# schemat1.net
KiCad netlist of a schematic drawn in EAGLE
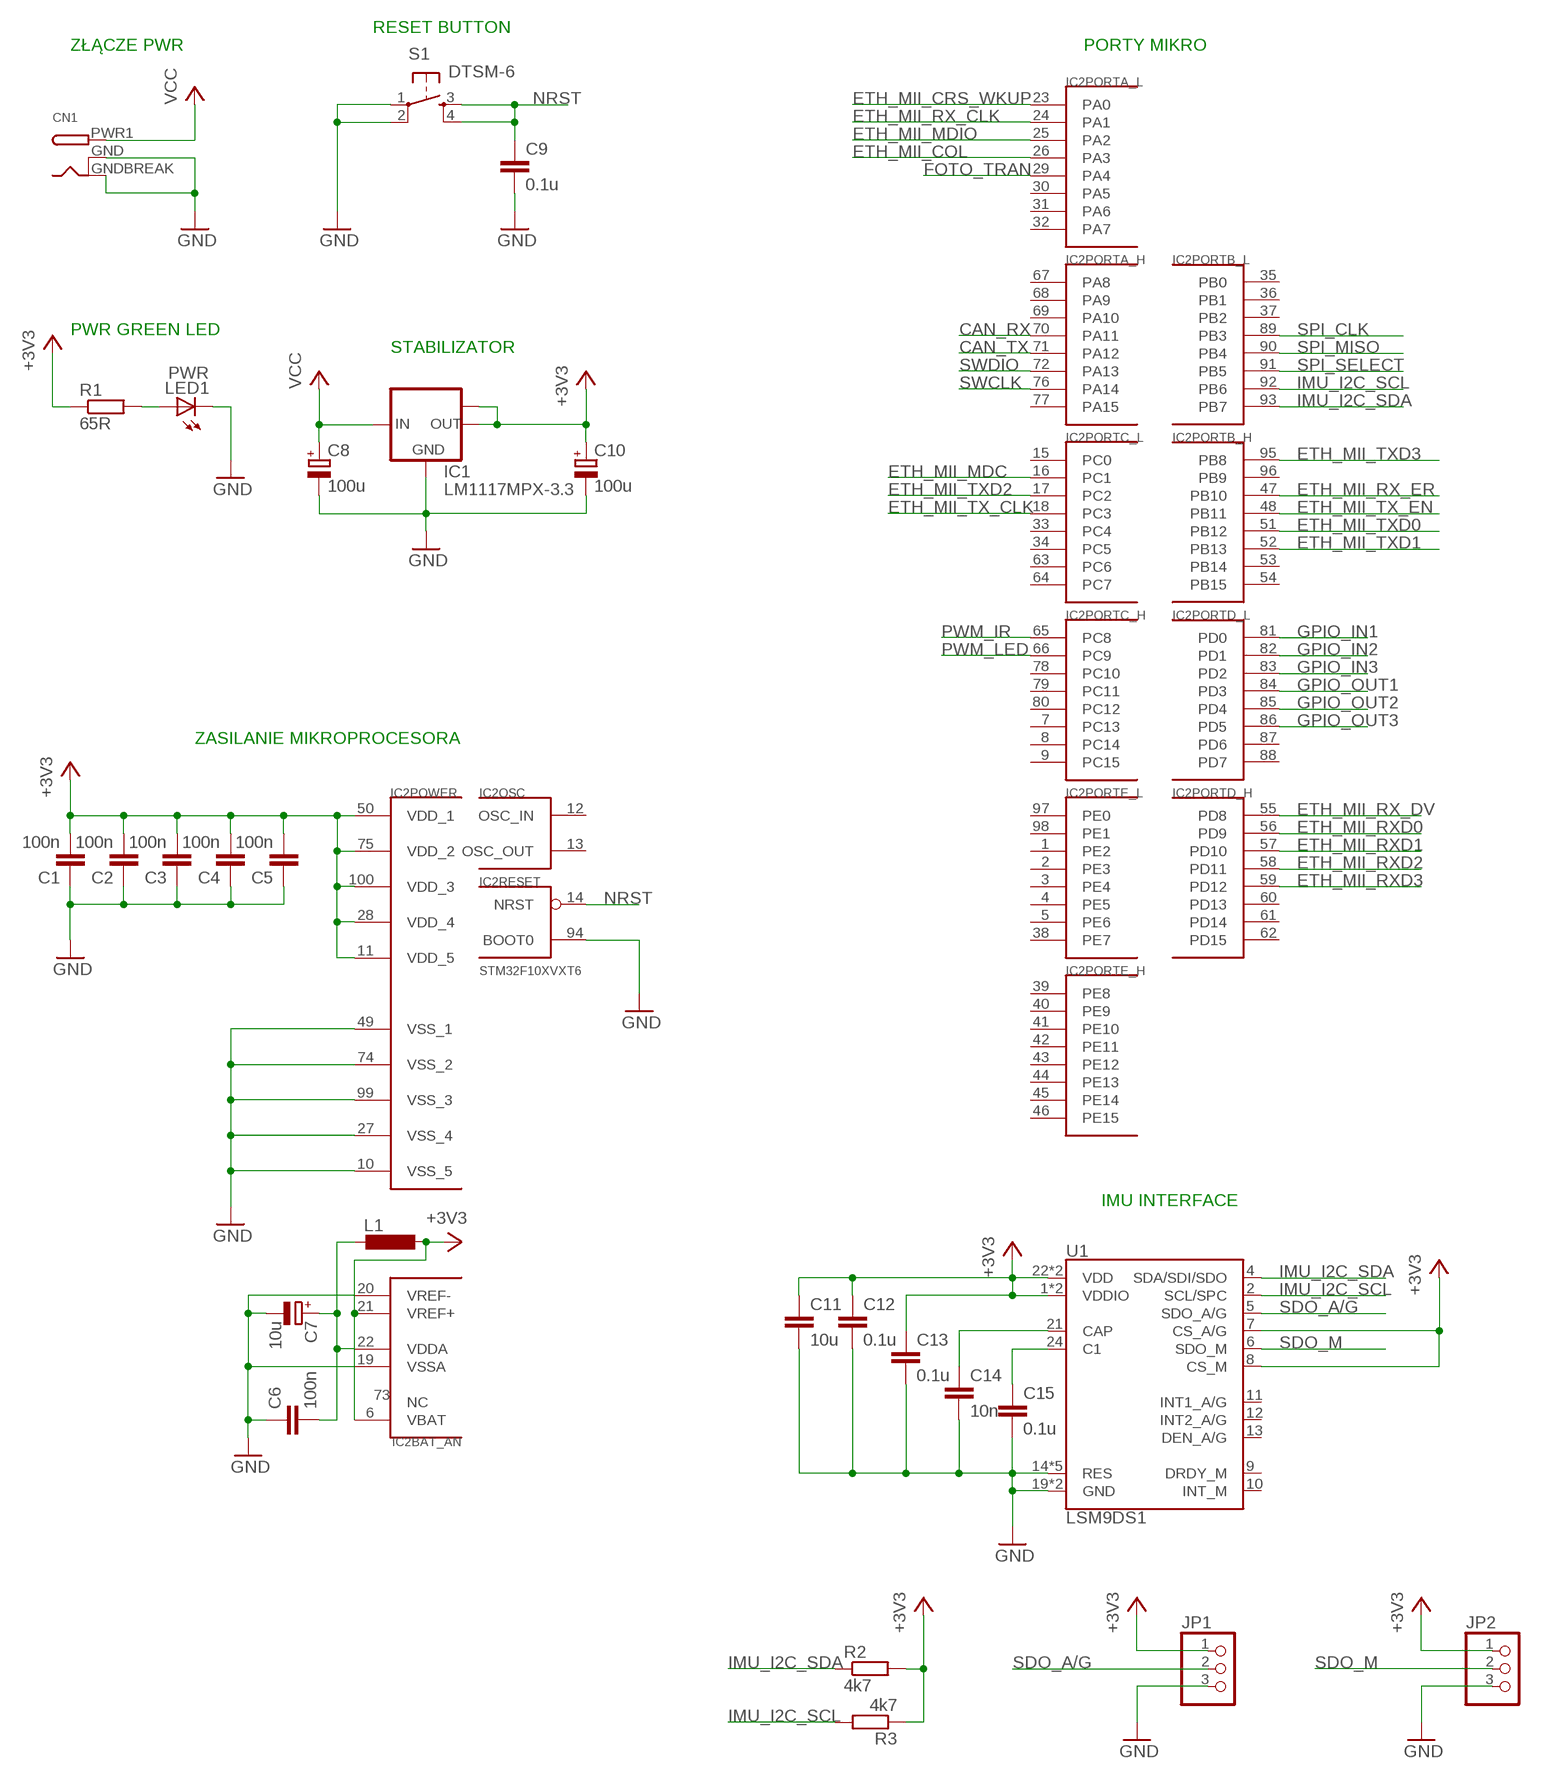
[diagram p0: schematic, sheet 1, part 1 of 2]
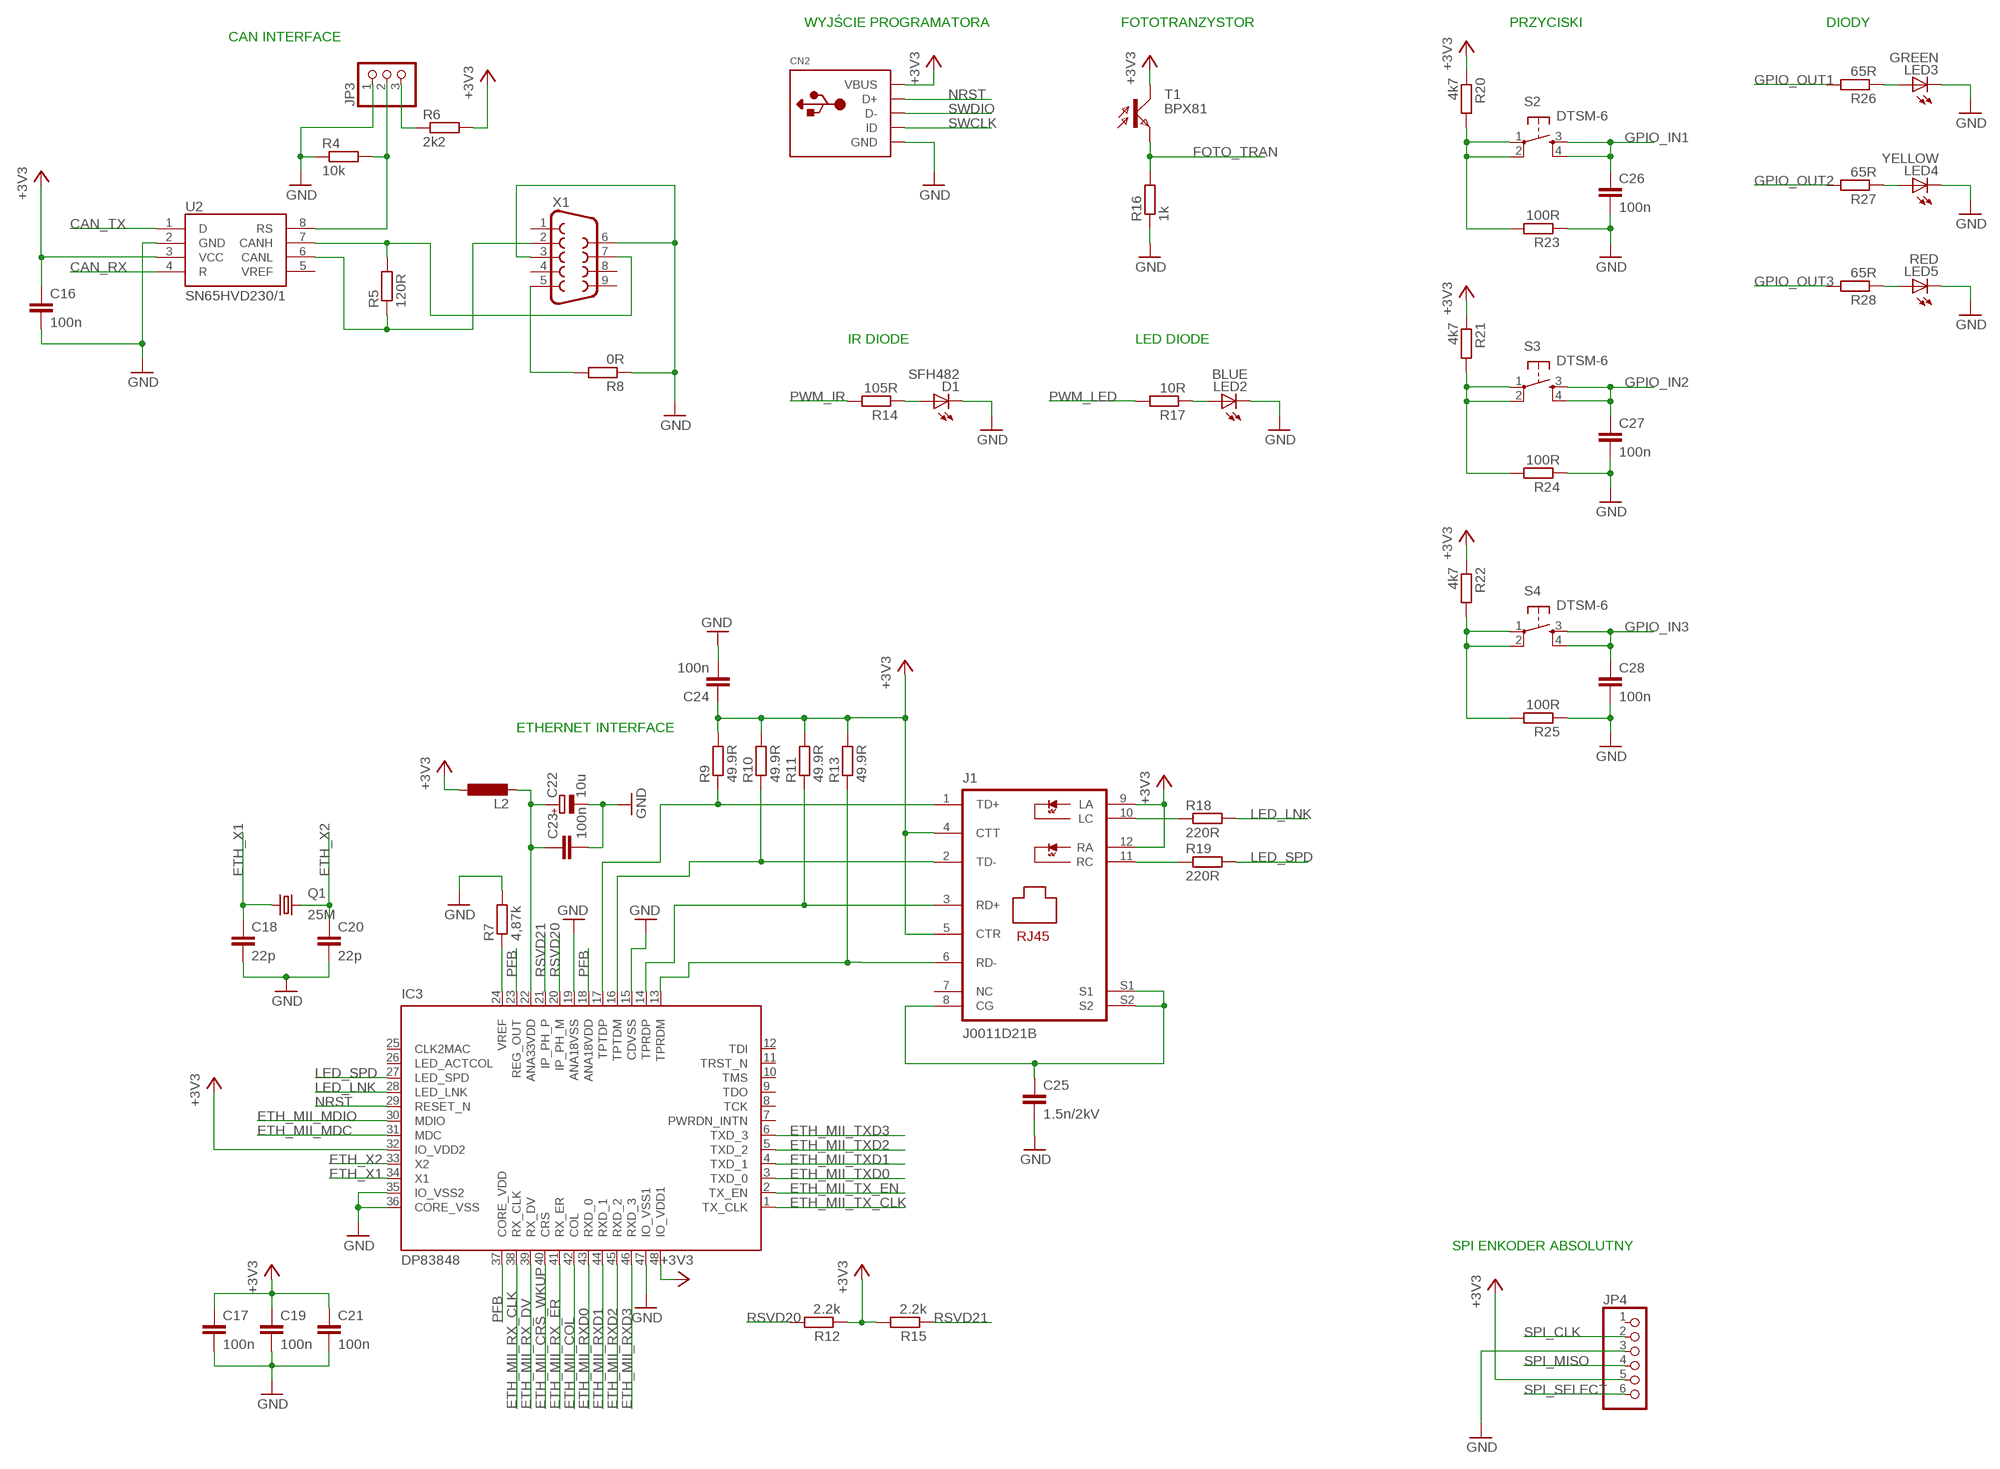
[diagram p1: schematic, sheet 1, part 2 of 2]

(export (version "E")
  (design (tool "Eeschema 10.0.6"))
  (components
    (comp (ref "C1")
      (value "100n")
      (footprint "eagle-import:C0805")
      (libsource (lib "eagle-import") (part "C-EUC0805"))
    )
    (comp (ref "C2")
      (value "100n")
      (footprint "eagle-import:C0805")
      (libsource (lib "eagle-import") (part "C-EUC0805"))
    )
    (comp (ref "C3")
      (value "100n")
      (footprint "eagle-import:C0805")
      (libsource (lib "eagle-import") (part "C-EUC0805"))
    )
    (comp (ref "C4")
      (value "100n")
      (footprint "eagle-import:C0805")
      (libsource (lib "eagle-import") (part "C-EUC0805"))
    )
    (comp (ref "C5")
      (value "100n")
      (footprint "eagle-import:C0805")
      (libsource (lib "eagle-import") (part "C-EUC0805"))
    )
    (comp (ref "C6")
      (value "100n")
      (footprint "eagle-import:C0805")
      (libsource (lib "eagle-import") (part "C-EUC0805"))
    )
    (comp (ref "C7")
      (value "10u")
      (footprint "eagle-import:PANASONIC_C")
      (libsource (lib "eagle-import") (part "CPOL-EUC"))
    )
    (comp (ref "C8")
      (value "100u")
      (footprint "eagle-import:PANASONIC_C")
      (libsource (lib "eagle-import") (part "CPOL-EUC"))
    )
    (comp (ref "C9")
      (value "0.1u")
      (footprint "eagle-import:C0805")
      (libsource (lib "eagle-import") (part "C-EUC0805"))
    )
    (comp (ref "C10")
      (value "100u")
      (footprint "eagle-import:PANASONIC_C")
      (libsource (lib "eagle-import") (part "CPOL-EUC"))
    )
    (comp (ref "C11")
      (value "10u")
      (footprint "eagle-import:C0805")
      (libsource (lib "eagle-import") (part "C-EUC0805"))
    )
    (comp (ref "C12")
      (value "0.1u")
      (footprint "eagle-import:C0805")
      (libsource (lib "eagle-import") (part "C-EUC0805"))
    )
    (comp (ref "C13")
      (value "0.1u")
      (footprint "eagle-import:C0805")
      (libsource (lib "eagle-import") (part "C-EUC0805"))
    )
    (comp (ref "C14")
      (value "10n")
      (footprint "eagle-import:C0805")
      (libsource (lib "eagle-import") (part "C-EUC0805"))
    )
    (comp (ref "C15")
      (value "0.1u")
      (footprint "eagle-import:C0805")
      (libsource (lib "eagle-import") (part "C-EUC0805"))
    )
    (comp (ref "C16")
      (value "100n")
      (footprint "eagle-import:C0805")
      (libsource (lib "eagle-import") (part "C-EUC0805"))
    )
    (comp (ref "C17")
      (value "100n")
      (footprint "eagle-import:C0805")
      (libsource (lib "eagle-import") (part "resistor_348_C-EUC0805"))
    )
    (comp (ref "C18")
      (value "22p")
      (footprint "eagle-import:C0805")
      (libsource (lib "eagle-import") (part "resistor_348_C-EUC0805"))
    )
    (comp (ref "C19")
      (value "100n")
      (footprint "eagle-import:C0805")
      (libsource (lib "eagle-import") (part "resistor_348_C-EUC0805"))
    )
    (comp (ref "C20")
      (value "22p")
      (footprint "eagle-import:C0805")
      (libsource (lib "eagle-import") (part "resistor_348_C-EUC0805"))
    )
    (comp (ref "C21")
      (value "100n")
      (footprint "eagle-import:C0805")
      (libsource (lib "eagle-import") (part "resistor_348_C-EUC0805"))
    )
    (comp (ref "C22")
      (value "10u")
      (footprint "eagle-import:PANASONIC_C")
      (libsource (lib "eagle-import") (part "CPOL-EUC"))
    )
    (comp (ref "C23")
      (value "100n")
      (footprint "eagle-import:C0805")
      (libsource (lib "eagle-import") (part "C-EUC0805"))
    )
    (comp (ref "C24")
      (value "100n")
      (footprint "eagle-import:C0805")
      (libsource (lib "eagle-import") (part "C-EUC0805"))
    )
    (comp (ref "C25")
      (value "1.5n/2kV")
      (footprint "eagle-import:C050-030X075")
      (libsource (lib "eagle-import") (part "C-EU050-030X075"))
    )
    (comp (ref "C26")
      (value "100n")
      (footprint "eagle-import:C0805")
      (libsource (lib "eagle-import") (part "C-EUC0805"))
    )
    (comp (ref "C27")
      (value "100n")
      (footprint "eagle-import:C0805")
      (libsource (lib "eagle-import") (part "C-EUC0805"))
    )
    (comp (ref "C28")
      (value "100n")
      (footprint "eagle-import:C0805")
      (libsource (lib "eagle-import") (part "C-EUC0805"))
    )
    (comp (ref "CN1")
      (value "DCBARRELSMT")
      (footprint "eagle-import:DCJACK_2MM_SMT")
      (libsource (lib "eagle-import") (part "DCBARRELSMT"))
    )
    (comp (ref "CN2")
      (value "USBMINIB")
      (footprint "eagle-import:USB-MINIB")
      (libsource (lib "eagle-import") (part "USBMINIB"))
    )
    (comp (ref "D1")
      (value "SFH482")
      (footprint "eagle-import:SFH482")
      (libsource (lib "eagle-import") (part "SFH482"))
    )
    (comp (ref "IC1")
      (value "LM1117MPX-3.3")
      (footprint "eagle-import:SOT223")
      (libsource (lib "eagle-import") (part "LM1117MPX-3.3"))
    )
    (comp (ref "IC2")
      (value "STM32F10XVXT6")
      (footprint "eagle-import:TQFP100")
      (libsource (lib "eagle-import") (part "STM32F10XVXT6"))
    )
    (comp (ref "IC3")
      (value "DP83848")
      (footprint "eagle-import:LQFP48")
      (fields (field (name "MPN") "DP83848VYB"))
      (libsource (lib "eagle-import") (part "DP83848"))
    )
    (comp (ref "J1")
      (value "J0011D21B")
      (footprint "eagle-import:J0-A_B_F")
      (libsource (lib "eagle-import") (part "J0011D21B"))
    )
    (comp (ref "JP1")
      (value "PINHD-1X3")
      (footprint "eagle-import:1X03")
      (libsource (lib "eagle-import") (part "pinhead_325_PINHD-1X3"))
    )
    (comp (ref "JP2")
      (value "PINHD-1X3")
      (footprint "eagle-import:1X03")
      (libsource (lib "eagle-import") (part "pinhead_325_PINHD-1X3"))
    )
    (comp (ref "JP3")
      (value "PINHD-1X3")
      (footprint "eagle-import:1X03")
      (libsource (lib "eagle-import") (part "PINHD-1X3"))
    )
    (comp (ref "JP4")
      (value "PINHD-1X6/90")
      (footprint "eagle-import:1X06_90")
      (libsource (lib "eagle-import") (part "PINHD-1X6/90"))
    )
    (comp (ref "L1")
      (value "L-EUL3230M")
      (footprint "eagle-import:L3230M")
      (libsource (lib "eagle-import") (part "L-EUL3230M"))
    )
    (comp (ref "L2")
      (value "L-EUL3230M")
      (footprint "eagle-import:L3230M")
      (libsource (lib "eagle-import") (part "L-EUL3230M"))
    )
    (comp (ref "LED1")
      (value "PWR")
      (footprint "eagle-import:CHIPLED_0805")
      (libsource (lib "eagle-import") (part "LEDCHIPLED_0805"))
    )
    (comp (ref "LED2")
      (value "BLUE")
      (footprint "eagle-import:LED5MM")
      (libsource (lib "eagle-import") (part "LED5MM"))
    )
    (comp (ref "LED3")
      (value "GREEN")
      (footprint "eagle-import:CHIPLED_0805")
      (libsource (lib "eagle-import") (part "LEDCHIPLED_0805"))
    )
    (comp (ref "LED4")
      (value "YELLOW")
      (footprint "eagle-import:CHIPLED_0805")
      (libsource (lib "eagle-import") (part "LEDCHIPLED_0805"))
    )
    (comp (ref "LED5")
      (value "RED")
      (footprint "eagle-import:CHIPLED_0805")
      (libsource (lib "eagle-import") (part "LEDCHIPLED_0805"))
    )
    (comp (ref "Q1")
      (value "25M")
      (footprint "eagle-import:3.2X2.5_KX-7")
      (libsource (lib "eagle-import") (part "KX-7"))
    )
    (comp (ref "R1")
      (value "65R")
      (footprint "eagle-import:R0805")
      (libsource (lib "eagle-import") (part "resistor_348_R-EU_R0805"))
    )
    (comp (ref "R2")
      (value "4k7")
      (footprint "eagle-import:M0805")
      (libsource (lib "eagle-import") (part "R-EU_M0805"))
    )
    (comp (ref "R3")
      (value "4k7")
      (footprint "eagle-import:M0805")
      (libsource (lib "eagle-import") (part "R-EU_M0805"))
    )
    (comp (ref "R4")
      (value "10k")
      (footprint "eagle-import:M0805")
      (libsource (lib "eagle-import") (part "resistor_348_R-EU_M0805"))
    )
    (comp (ref "R5")
      (value "120R")
      (footprint "eagle-import:M0805")
      (libsource (lib "eagle-import") (part "resistor_348_R-EU_M0805"))
    )
    (comp (ref "R6")
      (value "2k2")
      (footprint "eagle-import:M0805")
      (libsource (lib "eagle-import") (part "resistor_348_R-EU_M0805"))
    )
    (comp (ref "R7")
      (value "4,87k")
      (footprint "eagle-import:R0805")
      (libsource (lib "eagle-import") (part "resistor_348_R-EU_R0805"))
    )
    (comp (ref "R8")
      (value "0R")
      (footprint "eagle-import:R0805")
      (libsource (lib "eagle-import") (part "R-EU_R0805"))
    )
    (comp (ref "R9")
      (value "49.9R")
      (footprint "eagle-import:R0805")
      (libsource (lib "eagle-import") (part "resistor_348_R-EU_R0805"))
    )
    (comp (ref "R10")
      (value "49.9R")
      (footprint "eagle-import:R0805")
      (libsource (lib "eagle-import") (part "resistor_348_R-EU_R0805"))
    )
    (comp (ref "R11")
      (value "49.9R")
      (footprint "eagle-import:R0805")
      (libsource (lib "eagle-import") (part "resistor_348_R-EU_R0805"))
    )
    (comp (ref "R12")
      (value "2.2k")
      (footprint "eagle-import:R0805")
      (libsource (lib "eagle-import") (part "R-EU_R0805"))
    )
    (comp (ref "R13")
      (value "49.9R")
      (footprint "eagle-import:R0805")
      (libsource (lib "eagle-import") (part "resistor_348_R-EU_R0805"))
    )
    (comp (ref "R14")
      (value "105R")
      (footprint "eagle-import:M0805")
      (libsource (lib "eagle-import") (part "R-EU_M0805"))
    )
    (comp (ref "R15")
      (value "2.2k")
      (footprint "eagle-import:R0805")
      (libsource (lib "eagle-import") (part "R-EU_R0805"))
    )
    (comp (ref "R16")
      (value "1k")
      (footprint "eagle-import:R0805")
      (libsource (lib "eagle-import") (part "R-EU_R0805"))
    )
    (comp (ref "R17")
      (value "10R")
      (footprint "eagle-import:M0805")
      (libsource (lib "eagle-import") (part "R-EU_M0805"))
    )
    (comp (ref "R18")
      (value "220R")
      (footprint "eagle-import:R0805")
      (libsource (lib "eagle-import") (part "resistor_348_R-EU_R0805"))
    )
    (comp (ref "R19")
      (value "220R")
      (footprint "eagle-import:R0805")
      (libsource (lib "eagle-import") (part "resistor_348_R-EU_R0805"))
    )
    (comp (ref "R20")
      (value "4k7")
      (footprint "eagle-import:R0805")
      (libsource (lib "eagle-import") (part "R-EU_R0805"))
    )
    (comp (ref "R21")
      (value "4k7")
      (footprint "eagle-import:R0805")
      (libsource (lib "eagle-import") (part "R-EU_R0805"))
    )
    (comp (ref "R22")
      (value "4k7")
      (footprint "eagle-import:R0805")
      (libsource (lib "eagle-import") (part "R-EU_R0805"))
    )
    (comp (ref "R23")
      (value "100R")
      (footprint "eagle-import:R0805")
      (libsource (lib "eagle-import") (part "R-EU_R0805"))
    )
    (comp (ref "R24")
      (value "100R")
      (footprint "eagle-import:R0805")
      (libsource (lib "eagle-import") (part "R-EU_R0805"))
    )
    (comp (ref "R25")
      (value "100R")
      (footprint "eagle-import:R0805")
      (libsource (lib "eagle-import") (part "R-EU_R0805"))
    )
    (comp (ref "R26")
      (value "65R")
      (footprint "eagle-import:M0805")
      (libsource (lib "eagle-import") (part "R-EU_M0805"))
    )
    (comp (ref "R27")
      (value "65R")
      (footprint "eagle-import:M0805")
      (libsource (lib "eagle-import") (part "R-EU_M0805"))
    )
    (comp (ref "R28")
      (value "65R")
      (footprint "eagle-import:M0805")
      (libsource (lib "eagle-import") (part "R-EU_M0805"))
    )
    (comp (ref "S1")
      (value "DTSM-6")
      (footprint "eagle-import:DTSM-6")
      (libsource (lib "eagle-import") (part "DTSM-6"))
    )
    (comp (ref "S2")
      (value "DTSM-6")
      (footprint "eagle-import:DTSM-6")
      (libsource (lib "eagle-import") (part "DTSM-6"))
    )
    (comp (ref "S3")
      (value "DTSM-6")
      (footprint "eagle-import:DTSM-6")
      (libsource (lib "eagle-import") (part "DTSM-6"))
    )
    (comp (ref "S4")
      (value "DTSM-6")
      (footprint "eagle-import:DTSM-6")
      (libsource (lib "eagle-import") (part "DTSM-6"))
    )
    (comp (ref "T1")
      (value "BPX81")
      (footprint "eagle-import:BPX81")
      (libsource (lib "eagle-import") (part "BPX81"))
    )
    (comp (ref "U1")
      (value "LSM9DS1")
      (footprint "eagle-import:LGA24-8X4")
      (libsource (lib "eagle-import") (part "LSM9DS1"))
    )
    (comp (ref "U2")
      (value "SN65HVD230/1")
      (footprint "eagle-import:SO8")
      (libsource (lib "eagle-import") (part "SN65HVD230/1"))
    )
    (comp (ref "X1")
      (value "F09HP")
      (footprint "eagle-import:F09HP")
      (libsource (lib "eagle-import") (part "F09HP"))
    )
  )
  (nets
    (net (code "1") (name "+3V3") (class "Default")
      (node (ref "C1") (pin "2") (pinfunction "2_2") (pintype "passive"))
      (node (ref "C10") (pin "+") (pinfunction "+_+") (pintype "passive"))
      (node (ref "C11") (pin "1") (pinfunction "1_1") (pintype "passive"))
      (node (ref "C12") (pin "1") (pinfunction "1_1") (pintype "passive"))
      (node (ref "C13") (pin "1") (pinfunction "1_1") (pintype "passive"))
      (node (ref "C16") (pin "1") (pinfunction "1_1") (pintype "passive"))
      (node (ref "C17") (pin "1") (pinfunction "1_1") (pintype "passive"))
      (node (ref "C19") (pin "1") (pinfunction "1_1") (pintype "passive"))
      (node (ref "C2") (pin "2") (pinfunction "2_2") (pintype "passive"))
      (node (ref "C21") (pin "1") (pinfunction "1_1") (pintype "passive"))
      (node (ref "C24") (pin "1") (pinfunction "1_1") (pintype "passive"))
      (node (ref "C3") (pin "2") (pinfunction "2_2") (pintype "passive"))
      (node (ref "C4") (pin "2") (pinfunction "2_2") (pintype "passive"))
      (node (ref "C5") (pin "2") (pinfunction "2_2") (pintype "passive"))
      (node (ref "CN2") (pin "VBUS") (pinfunction "VBUS_VBUS") (pintype "power_in"))
      (node (ref "IC1") (pin "2") (pinfunction "OUT_2") (pintype "passive"))
      (node (ref "IC1") (pin "TAB") (pinfunction "OUT1_TAB") (pintype "passive"))
      (node (ref "IC2") (pin "100") (pinfunction "VDD_3_100") (pintype "power_in"))
      (node (ref "IC2") (pin "11") (pinfunction "VDD_5_11") (pintype "power_in"))
      (node (ref "IC2") (pin "21") (pinfunction "VREF+_21") (pintype "input"))
      (node (ref "IC2") (pin "28") (pinfunction "VDD_4_28") (pintype "power_in"))
      (node (ref "IC2") (pin "50") (pinfunction "VDD_1_50") (pintype "power_in"))
      (node (ref "IC2") (pin "6") (pinfunction "VBAT_6") (pintype "power_in"))
      (node (ref "IC2") (pin "75") (pinfunction "VDD_2_75") (pintype "power_in"))
      (node (ref "IC3") (pin "32") (pinfunction "IO_VDD2_32") (pintype "power_in"))
      (node (ref "IC3") (pin "48") (pinfunction "IO_VDD1_48") (pintype "power_in"))
      (node (ref "J1") (pin "12") (pinfunction "RA_12") (pintype "passive"))
      (node (ref "J1") (pin "4") (pinfunction "CTT_4") (pintype "passive"))
      (node (ref "J1") (pin "5") (pinfunction "CTR_5") (pintype "passive"))
      (node (ref "J1") (pin "9") (pinfunction "LA_9") (pintype "passive"))
      (node (ref "JP1") (pin "1") (pinfunction "1_1") (pintype "passive"))
      (node (ref "JP2") (pin "1") (pinfunction "1_1") (pintype "passive"))
      (node (ref "JP4") (pin "5") (pinfunction "5_5") (pintype "passive"))
      (node (ref "L1") (pin "1") (pinfunction "1_1") (pintype "passive"))
      (node (ref "L2") (pin "1") (pinfunction "1_1") (pintype "passive"))
      (node (ref "R1") (pin "1") (pinfunction "1_1") (pintype "passive"))
      (node (ref "R10") (pin "2") (pinfunction "2_2") (pintype "passive"))
      (node (ref "R11") (pin "2") (pinfunction "2_2") (pintype "passive"))
      (node (ref "R12") (pin "1") (pinfunction "1_1") (pintype "passive"))
      (node (ref "R13") (pin "2") (pinfunction "2_2") (pintype "passive"))
      (node (ref "R15") (pin "2") (pinfunction "2_2") (pintype "passive"))
      (node (ref "R2") (pin "2") (pinfunction "2_2") (pintype "passive"))
      (node (ref "R20") (pin "1") (pinfunction "1_1") (pintype "passive"))
      (node (ref "R21") (pin "1") (pinfunction "1_1") (pintype "passive"))
      (node (ref "R22") (pin "1") (pinfunction "1_1") (pintype "passive"))
      (node (ref "R3") (pin "1") (pinfunction "1_1") (pintype "passive"))
      (node (ref "R6") (pin "2") (pinfunction "2_2") (pintype "passive"))
      (node (ref "R9") (pin "2") (pinfunction "2_2") (pintype "passive"))
      (node (ref "T1") (pin "C") (pinfunction "C_C") (pintype "passive"))
      (node (ref "U1") (pin "1") (pinfunction "VDDIO_1") (pintype "bidirectional"))
      (node (ref "U1") (pin "22") (pinfunction "VDD_22") (pintype "bidirectional"))
      (node (ref "U1") (pin "23") (pinfunction "VDD_23") (pintype "bidirectional"))
      (node (ref "U1") (pin "3") (pinfunction "VDDIO_3") (pintype "bidirectional"))
      (node (ref "U1") (pin "7") (pinfunction "CS_A/G_7") (pintype "bidirectional"))
      (node (ref "U1") (pin "8") (pinfunction "CS_M_8") (pintype "bidirectional"))
      (node (ref "U2") (pin "3") (pinfunction "VCC_3") (pintype "power_in"))
    )
    (net (code "2") (name "/CAN_RX") (class "Default")
      (node (ref "IC2") (pin "70") (pinfunction "PA11_70") (pintype "bidirectional"))
      (node (ref "U2") (pin "4") (pinfunction "R_4") (pintype "bidirectional"))
    )
    (net (code "3") (name "/CAN_TX") (class "Default")
      (node (ref "IC2") (pin "71") (pinfunction "PA12_71") (pintype "bidirectional"))
      (node (ref "U2") (pin "1") (pinfunction "D_1") (pintype "bidirectional"))
    )
    (net (code "4") (name "/ETH_MII_COL") (class "Default")
      (node (ref "IC2") (pin "26") (pinfunction "PA3_26") (pintype "bidirectional"))
      (node (ref "IC3") (pin "42") (pinfunction "COL_42") (pintype "bidirectional"))
    )
    (net (code "5") (name "/ETH_MII_CRS_WKUP") (class "Default")
      (node (ref "IC2") (pin "23") (pinfunction "PA0_23") (pintype "bidirectional"))
      (node (ref "IC3") (pin "40") (pinfunction "CRS_40") (pintype "bidirectional"))
    )
    (net (code "6") (name "/ETH_MII_MDC") (class "Default")
      (node (ref "IC2") (pin "16") (pinfunction "PC1_16") (pintype "bidirectional"))
      (node (ref "IC3") (pin "31") (pinfunction "MDC_31") (pintype "input"))
    )
    (net (code "7") (name "/ETH_MII_MDIO") (class "Default")
      (node (ref "IC2") (pin "25") (pinfunction "PA2_25") (pintype "bidirectional"))
      (node (ref "IC3") (pin "30") (pinfunction "MDIO_30") (pintype "bidirectional"))
    )
    (net (code "8") (name "/ETH_MII_RXD0") (class "Default")
      (node (ref "IC2") (pin "56") (pinfunction "PD9_56") (pintype "bidirectional"))
      (node (ref "IC3") (pin "43") (pinfunction "RXD_0_43") (pintype "bidirectional"))
    )
    (net (code "9") (name "/ETH_MII_RXD1") (class "Default")
      (node (ref "IC2") (pin "57") (pinfunction "PD10_57") (pintype "bidirectional"))
      (node (ref "IC3") (pin "44") (pinfunction "RXD_1_44") (pintype "bidirectional"))
    )
    (net (code "10") (name "/ETH_MII_RXD2") (class "Default")
      (node (ref "IC2") (pin "58") (pinfunction "PD11_58") (pintype "bidirectional"))
      (node (ref "IC3") (pin "45") (pinfunction "RXD_2_45") (pintype "bidirectional"))
    )
    (net (code "11") (name "/ETH_MII_RXD3") (class "Default")
      (node (ref "IC2") (pin "59") (pinfunction "PD12_59") (pintype "bidirectional"))
      (node (ref "IC3") (pin "46") (pinfunction "RXD_3_46") (pintype "bidirectional"))
    )
    (net (code "12") (name "/ETH_MII_RX_CLK") (class "Default")
      (node (ref "IC2") (pin "24") (pinfunction "PA1_24") (pintype "bidirectional"))
      (node (ref "IC3") (pin "38") (pinfunction "RX_CLK_38") (pintype "bidirectional"))
    )
    (net (code "13") (name "/ETH_MII_RX_DV") (class "Default")
      (node (ref "IC2") (pin "55") (pinfunction "PD8_55") (pintype "bidirectional"))
      (node (ref "IC3") (pin "39") (pinfunction "RX_DV_39") (pintype "bidirectional"))
    )
    (net (code "14") (name "/ETH_MII_RX_ER") (class "Default")
      (node (ref "IC2") (pin "47") (pinfunction "PB10_47") (pintype "bidirectional"))
      (node (ref "IC3") (pin "41") (pinfunction "RX_ER_41") (pintype "bidirectional"))
    )
    (net (code "15") (name "/ETH_MII_TXD0") (class "Default")
      (node (ref "IC2") (pin "51") (pinfunction "PB12_51") (pintype "bidirectional"))
      (node (ref "IC3") (pin "3") (pinfunction "TXD_0_3") (pintype "bidirectional"))
    )
    (net (code "16") (name "/ETH_MII_TXD1") (class "Default")
      (node (ref "IC2") (pin "52") (pinfunction "PB13_52") (pintype "bidirectional"))
      (node (ref "IC3") (pin "4") (pinfunction "TXD_1_4") (pintype "bidirectional"))
    )
    (net (code "17") (name "/ETH_MII_TXD2") (class "Default")
      (node (ref "IC2") (pin "17") (pinfunction "PC2_17") (pintype "bidirectional"))
      (node (ref "IC3") (pin "5") (pinfunction "TXD_2_5") (pintype "bidirectional"))
    )
    (net (code "18") (name "/ETH_MII_TXD3") (class "Default")
      (node (ref "IC2") (pin "95") (pinfunction "PB8_95") (pintype "bidirectional"))
      (node (ref "IC3") (pin "6") (pinfunction "TXD_3_6") (pintype "bidirectional"))
    )
    (net (code "19") (name "/ETH_MII_TX_CLK") (class "Default")
      (node (ref "IC2") (pin "18") (pinfunction "PC3_18") (pintype "bidirectional"))
      (node (ref "IC3") (pin "1") (pinfunction "TX_CLK_1") (pintype "bidirectional"))
    )
    (net (code "20") (name "/ETH_MII_TX_EN") (class "Default")
      (node (ref "IC2") (pin "48") (pinfunction "PB11_48") (pintype "bidirectional"))
      (node (ref "IC3") (pin "2") (pinfunction "TX_EN_2") (pintype "bidirectional"))
    )
    (net (code "21") (name "/ETH_X1") (class "Default")
      (node (ref "C18") (pin "1") (pinfunction "1_1") (pintype "passive"))
      (node (ref "IC3") (pin "34") (pinfunction "X1_34") (pintype "input"))
      (node (ref "Q1") (pin "1") (pinfunction "1_1") (pintype "passive"))
    )
    (net (code "22") (name "/ETH_X2") (class "Default")
      (node (ref "C20") (pin "1") (pinfunction "1_1") (pintype "passive"))
      (node (ref "IC3") (pin "33") (pinfunction "X2_33") (pintype "output"))
      (node (ref "Q1") (pin "3") (pinfunction "2_3") (pintype "passive"))
    )
    (net (code "23") (name "/FOTO_TRAN") (class "Default")
      (node (ref "IC2") (pin "29") (pinfunction "PA4_29") (pintype "bidirectional"))
      (node (ref "R16") (pin "2") (pinfunction "2_2") (pintype "passive"))
      (node (ref "T1") (pin "E") (pinfunction "E_E") (pintype "passive"))
    )
    (net (code "24") (name "/GPIO_IN1") (class "Default")
      (node (ref "C26") (pin "1") (pinfunction "1_1") (pintype "passive"))
      (node (ref "IC2") (pin "81") (pinfunction "PD0_81") (pintype "bidirectional"))
      (node (ref "S2") (pin "3") (pinfunction "3_3") (pintype "passive"))
      (node (ref "S2") (pin "4") (pinfunction "4_4") (pintype "passive"))
    )
    (net (code "25") (name "/GPIO_IN2") (class "Default")
      (node (ref "C27") (pin "1") (pinfunction "1_1") (pintype "passive"))
      (node (ref "IC2") (pin "82") (pinfunction "PD1_82") (pintype "bidirectional"))
      (node (ref "S3") (pin "3") (pinfunction "3_3") (pintype "passive"))
      (node (ref "S3") (pin "4") (pinfunction "4_4") (pintype "passive"))
    )
    (net (code "26") (name "/GPIO_IN3") (class "Default")
      (node (ref "C28") (pin "1") (pinfunction "1_1") (pintype "passive"))
      (node (ref "IC2") (pin "83") (pinfunction "PD2_83") (pintype "bidirectional"))
      (node (ref "S4") (pin "3") (pinfunction "3_3") (pintype "passive"))
      (node (ref "S4") (pin "4") (pinfunction "4_4") (pintype "passive"))
    )
    (net (code "27") (name "/GPIO_OUT1") (class "Default")
      (node (ref "IC2") (pin "84") (pinfunction "PD3_84") (pintype "bidirectional"))
      (node (ref "R26") (pin "2") (pinfunction "2_2") (pintype "passive"))
    )
    (net (code "28") (name "/GPIO_OUT2") (class "Default")
      (node (ref "IC2") (pin "85") (pinfunction "PD4_85") (pintype "bidirectional"))
      (node (ref "R27") (pin "2") (pinfunction "2_2") (pintype "passive"))
    )
    (net (code "29") (name "/GPIO_OUT3") (class "Default")
      (node (ref "IC2") (pin "86") (pinfunction "PD5_86") (pintype "bidirectional"))
      (node (ref "R28") (pin "2") (pinfunction "2_2") (pintype "passive"))
    )
    (net (code "30") (name "/IMU_I2C_SCL") (class "Default")
      (node (ref "IC2") (pin "92") (pinfunction "PB6_92") (pintype "bidirectional"))
      (node (ref "R3") (pin "2") (pinfunction "2_2") (pintype "passive"))
      (node (ref "U1") (pin "2") (pinfunction "SCL/SPC_2") (pintype "bidirectional"))
    )
    (net (code "31") (name "/IMU_I2C_SDA") (class "Default")
      (node (ref "IC2") (pin "93") (pinfunction "PB7_93") (pintype "bidirectional"))
      (node (ref "R2") (pin "1") (pinfunction "1_1") (pintype "passive"))
      (node (ref "U1") (pin "4") (pinfunction "SDA/SDI/SDO_4") (pintype "bidirectional"))
    )
    (net (code "32") (name "/LED_LNK") (class "Default")
      (node (ref "IC3") (pin "28") (pinfunction "LED_LNK_28") (pintype "bidirectional"))
      (node (ref "R18") (pin "2") (pinfunction "2_2") (pintype "passive"))
    )
    (net (code "33") (name "/LED_SPD") (class "Default")
      (node (ref "IC3") (pin "27") (pinfunction "LED_SPD_27") (pintype "bidirectional"))
      (node (ref "R19") (pin "2") (pinfunction "2_2") (pintype "passive"))
    )
    (net (code "34") (name "/NRST") (class "Default")
      (node (ref "C9") (pin "1") (pinfunction "1_1") (pintype "passive"))
      (node (ref "CN2") (pin "D+") (pinfunction "D+_D+") (pintype "bidirectional"))
      (node (ref "IC2") (pin "14") (pinfunction "NRST_14") (pintype "input"))
      (node (ref "IC3") (pin "29") (pinfunction "RESET_N_29") (pintype "input"))
      (node (ref "S1") (pin "3") (pinfunction "3_3") (pintype "passive"))
      (node (ref "S1") (pin "4") (pinfunction "4_4") (pintype "passive"))
    )
    (net (code "35") (name "/PFB") (class "Default")
      (node (ref "IC3") (pin "18") (pinfunction "ANA18VDD_18") (pintype "power_in"))
      (node (ref "IC3") (pin "23") (pinfunction "REG_OUT_23") (pintype "output"))
      (node (ref "IC3") (pin "37") (pinfunction "CORE_VDD_37") (pintype "power_in"))
    )
    (net (code "36") (name "/PWM_IR") (class "Default")
      (node (ref "IC2") (pin "65") (pinfunction "PC8_65") (pintype "bidirectional"))
      (node (ref "R14") (pin "2") (pinfunction "2_2") (pintype "passive"))
    )
    (net (code "37") (name "/PWM_LED") (class "Default")
      (node (ref "IC2") (pin "66") (pinfunction "PC9_66") (pintype "bidirectional"))
      (node (ref "R17") (pin "2") (pinfunction "2_2") (pintype "passive"))
    )
    (net (code "38") (name "/RSVD20") (class "Default")
      (node (ref "IC3") (pin "20") (pinfunction "IP_PH_M_20") (pintype "input"))
      (node (ref "R12") (pin "2") (pinfunction "2_2") (pintype "passive"))
    )
    (net (code "39") (name "/RSVD21") (class "Default")
      (node (ref "IC3") (pin "21") (pinfunction "IP_PH_P_21") (pintype "input"))
      (node (ref "R15") (pin "1") (pinfunction "1_1") (pintype "passive"))
    )
    (net (code "40") (name "/SDO_A{slash}G") (class "Default")
      (node (ref "JP1") (pin "2") (pinfunction "2_2") (pintype "passive"))
      (node (ref "U1") (pin "5") (pinfunction "SDO_A/G_5") (pintype "bidirectional"))
    )
    (net (code "41") (name "/SDO_M") (class "Default")
      (node (ref "JP2") (pin "2") (pinfunction "2_2") (pintype "passive"))
      (node (ref "U1") (pin "6") (pinfunction "SDO_M_6") (pintype "bidirectional"))
    )
    (net (code "42") (name "/SPI_CLK") (class "Default")
      (node (ref "IC2") (pin "89") (pinfunction "PB3_89") (pintype "bidirectional"))
      (node (ref "JP4") (pin "2") (pinfunction "2_2") (pintype "passive"))
    )
    (net (code "43") (name "/SPI_MISO") (class "Default")
      (node (ref "IC2") (pin "90") (pinfunction "PB4_90") (pintype "bidirectional"))
      (node (ref "JP4") (pin "4") (pinfunction "4_4") (pintype "passive"))
    )
    (net (code "44") (name "/SPI_SELECT") (class "Default")
      (node (ref "IC2") (pin "91") (pinfunction "PB5_91") (pintype "bidirectional"))
      (node (ref "JP4") (pin "6") (pinfunction "6_6") (pintype "passive"))
    )
    (net (code "45") (name "/SWCLK") (class "Default")
      (node (ref "CN2") (pin "ID") (pinfunction "ID_ID") (pintype "bidirectional"))
      (node (ref "IC2") (pin "76") (pinfunction "PA14_76") (pintype "bidirectional"))
    )
    (net (code "46") (name "/SWDIO") (class "Default")
      (node (ref "CN2") (pin "D-") (pinfunction "D-_D-") (pintype "bidirectional"))
      (node (ref "IC2") (pin "72") (pinfunction "PA13_72") (pintype "bidirectional"))
    )
    (net (code "47") (name "GND") (class "Default")
      (node (ref "C1") (pin "1") (pinfunction "1_1") (pintype "passive"))
      (node (ref "C10") (pin "-") (pinfunction "-_-") (pintype "passive"))
      (node (ref "C11") (pin "2") (pinfunction "2_2") (pintype "passive"))
      (node (ref "C12") (pin "2") (pinfunction "2_2") (pintype "passive"))
      (node (ref "C13") (pin "2") (pinfunction "2_2") (pintype "passive"))
      (node (ref "C14") (pin "2") (pinfunction "2_2") (pintype "passive"))
      (node (ref "C15") (pin "2") (pinfunction "2_2") (pintype "passive"))
      (node (ref "C16") (pin "2") (pinfunction "2_2") (pintype "passive"))
      (node (ref "C17") (pin "2") (pinfunction "2_2") (pintype "passive"))
      (node (ref "C18") (pin "2") (pinfunction "2_2") (pintype "passive"))
      (node (ref "C19") (pin "2") (pinfunction "2_2") (pintype "passive"))
      (node (ref "C2") (pin "1") (pinfunction "1_1") (pintype "passive"))
      (node (ref "C20") (pin "2") (pinfunction "2_2") (pintype "passive"))
      (node (ref "C21") (pin "2") (pinfunction "2_2") (pintype "passive"))
      (node (ref "C22") (pin "-") (pinfunction "-_-") (pintype "passive"))
      (node (ref "C23") (pin "2") (pinfunction "2_2") (pintype "passive"))
      (node (ref "C24") (pin "2") (pinfunction "2_2") (pintype "passive"))
      (node (ref "C25") (pin "2") (pinfunction "2_2") (pintype "passive"))
      (node (ref "C26") (pin "2") (pinfunction "2_2") (pintype "passive"))
      (node (ref "C27") (pin "2") (pinfunction "2_2") (pintype "passive"))
      (node (ref "C28") (pin "2") (pinfunction "2_2") (pintype "passive"))
      (node (ref "C3") (pin "1") (pinfunction "1_1") (pintype "passive"))
      (node (ref "C4") (pin "1") (pinfunction "1_1") (pintype "passive"))
      (node (ref "C5") (pin "1") (pinfunction "1_1") (pintype "passive"))
      (node (ref "C6") (pin "1") (pinfunction "1_1") (pintype "passive"))
      (node (ref "C7") (pin "-") (pinfunction "-_-") (pintype "passive"))
      (node (ref "C8") (pin "-") (pinfunction "-_-") (pintype "passive"))
      (node (ref "C9") (pin "2") (pinfunction "2_2") (pintype "passive"))
      (node (ref "CN1") (pin "GND") (pinfunction "GNDBREAK_GND") (pintype "power_in"))
      (node (ref "CN1") (pin "GNDBREAK") (pinfunction "GND_GNDBREAK") (pintype "power_in"))
      (node (ref "CN2") (pin "GND") (pinfunction "GND_GND") (pintype "power_in"))
      (node (ref "D1") (pin "K") (pinfunction "C_K") (pintype "passive"))
      (node (ref "IC1") (pin "1") (pinfunction "GND_1") (pintype "input"))
      (node (ref "IC2") (pin "10") (pinfunction "VSS_5_10") (pintype "power_in"))
      (node (ref "IC2") (pin "19") (pinfunction "VSSA_19") (pintype "power_in"))
      (node (ref "IC2") (pin "20") (pinfunction "VREF-_20") (pintype "input"))
      (node (ref "IC2") (pin "27") (pinfunction "VSS_4_27") (pintype "power_in"))
      (node (ref "IC2") (pin "49") (pinfunction "VSS_1_49") (pintype "power_in"))
      (node (ref "IC2") (pin "74") (pinfunction "VSS_2_74") (pintype "power_in"))
      (node (ref "IC2") (pin "94") (pinfunction "BOOT0_94") (pintype "input"))
      (node (ref "IC2") (pin "99") (pinfunction "VSS_3_99") (pintype "power_in"))
      (node (ref "IC3") (pin "15") (pinfunction "CDVSS_15") (pintype "power_in"))
      (node (ref "IC3") (pin "19") (pinfunction "ANA18VSS_19") (pintype "power_in"))
      (node (ref "IC3") (pin "35") (pinfunction "IO_VSS2_35") (pintype "power_in"))
      (node (ref "IC3") (pin "36") (pinfunction "CORE_VSS_36") (pintype "power_in"))
      (node (ref "IC3") (pin "47") (pinfunction "IO_VSS1_47") (pintype "power_in"))
      (node (ref "JP1") (pin "3") (pinfunction "3_3") (pintype "passive"))
      (node (ref "JP2") (pin "3") (pinfunction "3_3") (pintype "passive"))
      (node (ref "JP3") (pin "1") (pinfunction "1_1") (pintype "passive"))
      (node (ref "JP4") (pin "3") (pinfunction "3_3") (pintype "passive"))
      (node (ref "LED1") (pin "C") (pinfunction "C_C") (pintype "passive"))
      (node (ref "LED2") (pin "K") (pinfunction "C_K") (pintype "passive"))
      (node (ref "LED3") (pin "C") (pinfunction "C_C") (pintype "passive"))
      (node (ref "LED4") (pin "C") (pinfunction "C_C") (pintype "passive"))
      (node (ref "LED5") (pin "C") (pinfunction "C_C") (pintype "passive"))
      (node (ref "R16") (pin "1") (pinfunction "1_1") (pintype "passive"))
      (node (ref "R23") (pin "1") (pinfunction "1_1") (pintype "passive"))
      (node (ref "R24") (pin "1") (pinfunction "1_1") (pintype "passive"))
      (node (ref "R25") (pin "1") (pinfunction "1_1") (pintype "passive"))
      (node (ref "R4") (pin "1") (pinfunction "1_1") (pintype "passive"))
      (node (ref "R7") (pin "2") (pinfunction "2_2") (pintype "passive"))
      (node (ref "R8") (pin "1") (pinfunction "1_1") (pintype "passive"))
      (node (ref "S1") (pin "1") (pinfunction "1_1") (pintype "passive"))
      (node (ref "S1") (pin "2") (pinfunction "2_2") (pintype "passive"))
      (node (ref "U1") (pin "14") (pinfunction "RES_14") (pintype "bidirectional"))
      (node (ref "U1") (pin "15") (pinfunction "RES_15") (pintype "bidirectional"))
      (node (ref "U1") (pin "16") (pinfunction "RES_16") (pintype "bidirectional"))
      (node (ref "U1") (pin "17") (pinfunction "RES_17") (pintype "bidirectional"))
      (node (ref "U1") (pin "18") (pinfunction "RES_18") (pintype "bidirectional"))
      (node (ref "U1") (pin "19") (pinfunction "GND_19") (pintype "bidirectional"))
      (node (ref "U1") (pin "20") (pinfunction "GND_20") (pintype "bidirectional"))
      (node (ref "U2") (pin "2") (pinfunction "GND_2") (pintype "power_in"))
      (node (ref "X1") (pin "3") (pinfunction "3_3") (pintype "passive"))
      (node (ref "X1") (pin "6") (pinfunction "6_6") (pintype "passive"))
    )
    (net (code "48") (name "Net-(D1-PadA)") (class "Default")
      (node (ref "D1") (pin "A") (pinfunction "A_A") (pintype "passive"))
      (node (ref "R14") (pin "1") (pinfunction "1_1") (pintype "passive"))
    )
    (net (code "49") (name "Net-(IC2A-VDDA)") (class "Default")
      (node (ref "C6") (pin "2") (pinfunction "2_2") (pintype "passive"))
      (node (ref "C7") (pin "+") (pinfunction "+_+") (pintype "passive"))
      (node (ref "IC2") (pin "22") (pinfunction "VDDA_22") (pintype "power_in"))
      (node (ref "L1") (pin "2") (pinfunction "2_2") (pintype "passive"))
    )
    (net (code "50") (name "Net-(IC3-ANA33VDD)") (class "Default")
      (node (ref "C22") (pin "+") (pinfunction "+_+") (pintype "passive"))
      (node (ref "C23") (pin "1") (pinfunction "1_1") (pintype "passive"))
      (node (ref "IC3") (pin "22") (pinfunction "ANA33VDD_22") (pintype "power_in"))
      (node (ref "L2") (pin "2") (pinfunction "2_2") (pintype "passive"))
    )
    (net (code "51") (name "Net-(IC3-TPRDM)") (class "Default")
      (node (ref "IC3") (pin "13") (pinfunction "TPRDM_13") (pintype "bidirectional"))
      (node (ref "J1") (pin "6") (pinfunction "RD-_6") (pintype "passive"))
      (node (ref "R13") (pin "1") (pinfunction "1_1") (pintype "passive"))
    )
    (net (code "52") (name "Net-(IC3-TPRDP)") (class "Default")
      (node (ref "IC3") (pin "14") (pinfunction "TPRDP_14") (pintype "bidirectional"))
      (node (ref "J1") (pin "3") (pinfunction "RD+_3") (pintype "passive"))
      (node (ref "R11") (pin "1") (pinfunction "1_1") (pintype "passive"))
    )
    (net (code "53") (name "Net-(IC3-TPTDM)") (class "Default")
      (node (ref "IC3") (pin "16") (pinfunction "TPTDM_16") (pintype "bidirectional"))
      (node (ref "J1") (pin "2") (pinfunction "TD-_2") (pintype "passive"))
      (node (ref "R10") (pin "1") (pinfunction "1_1") (pintype "passive"))
    )
    (net (code "54") (name "Net-(IC3-TPTDP)") (class "Default")
      (node (ref "IC3") (pin "17") (pinfunction "TPTDP_17") (pintype "bidirectional"))
      (node (ref "J1") (pin "1") (pinfunction "TD+_1") (pintype "passive"))
      (node (ref "R9") (pin "1") (pinfunction "1_1") (pintype "passive"))
    )
    (net (code "55") (name "Net-(IC3-VREF)") (class "Default")
      (node (ref "IC3") (pin "24") (pinfunction "VREF_24") (pintype "bidirectional"))
      (node (ref "R7") (pin "1") (pinfunction "1_1") (pintype "passive"))
    )
    (net (code "56") (name "Net-(J1-CG)") (class "Default")
      (node (ref "C25") (pin "1") (pinfunction "1_1") (pintype "passive"))
      (node (ref "J1") (pin "8") (pinfunction "CG_8") (pintype "passive"))
      (node (ref "J1") (pin "S1") (pinfunction "S1_S1") (pintype "passive"))
      (node (ref "J1") (pin "S2") (pinfunction "S2_S2") (pintype "passive"))
    )
    (net (code "57") (name "Net-(J1-LC)") (class "Default")
      (node (ref "J1") (pin "10") (pinfunction "LC_10") (pintype "passive"))
      (node (ref "R18") (pin "1") (pinfunction "1_1") (pintype "passive"))
    )
    (net (code "58") (name "Net-(J1-RC)") (class "Default")
      (node (ref "J1") (pin "11") (pinfunction "RC_11") (pintype "passive"))
      (node (ref "R19") (pin "1") (pinfunction "1_1") (pintype "passive"))
    )
    (net (code "59") (name "Net-(JP3-Pad3)") (class "Default")
      (node (ref "JP3") (pin "3") (pinfunction "3_3") (pintype "passive"))
      (node (ref "R6") (pin "1") (pinfunction "1_1") (pintype "passive"))
    )
    (net (code "60") (name "Net-(LED1-PadA)") (class "Default")
      (node (ref "LED1") (pin "A") (pinfunction "A_A") (pintype "passive"))
      (node (ref "R1") (pin "2") (pinfunction "2_2") (pintype "passive"))
    )
    (net (code "61") (name "Net-(LED2-PadA)") (class "Default")
      (node (ref "LED2") (pin "A") (pinfunction "A_A") (pintype "passive"))
      (node (ref "R17") (pin "1") (pinfunction "1_1") (pintype "passive"))
    )
    (net (code "62") (name "Net-(LED3-PadA)") (class "Default")
      (node (ref "LED3") (pin "A") (pinfunction "A_A") (pintype "passive"))
      (node (ref "R26") (pin "1") (pinfunction "1_1") (pintype "passive"))
    )
    (net (code "63") (name "Net-(LED4-PadA)") (class "Default")
      (node (ref "LED4") (pin "A") (pinfunction "A_A") (pintype "passive"))
      (node (ref "R27") (pin "1") (pinfunction "1_1") (pintype "passive"))
    )
    (net (code "64") (name "Net-(LED5-PadA)") (class "Default")
      (node (ref "LED5") (pin "A") (pinfunction "A_A") (pintype "passive"))
      (node (ref "R28") (pin "1") (pinfunction "1_1") (pintype "passive"))
    )
    (net (code "65") (name "Net-(R8-Pad2)") (class "Default")
      (node (ref "R8") (pin "2") (pinfunction "2_2") (pintype "passive"))
      (node (ref "X1") (pin "5") (pinfunction "5_5") (pintype "passive"))
    )
    (net (code "66") (name "Net-(R20-Pad2)") (class "Default")
      (node (ref "R20") (pin "2") (pinfunction "2_2") (pintype "passive"))
      (node (ref "R23") (pin "2") (pinfunction "2_2") (pintype "passive"))
      (node (ref "S2") (pin "1") (pinfunction "1_1") (pintype "passive"))
      (node (ref "S2") (pin "2") (pinfunction "2_2") (pintype "passive"))
    )
    (net (code "67") (name "Net-(R21-Pad2)") (class "Default")
      (node (ref "R21") (pin "2") (pinfunction "2_2") (pintype "passive"))
      (node (ref "R24") (pin "2") (pinfunction "2_2") (pintype "passive"))
      (node (ref "S3") (pin "1") (pinfunction "1_1") (pintype "passive"))
      (node (ref "S3") (pin "2") (pinfunction "2_2") (pintype "passive"))
    )
    (net (code "68") (name "Net-(R22-Pad2)") (class "Default")
      (node (ref "R22") (pin "2") (pinfunction "2_2") (pintype "passive"))
      (node (ref "R25") (pin "2") (pinfunction "2_2") (pintype "passive"))
      (node (ref "S4") (pin "1") (pinfunction "1_1") (pintype "passive"))
      (node (ref "S4") (pin "2") (pinfunction "2_2") (pintype "passive"))
    )
    (net (code "69") (name "Net-(U1-C1)") (class "Default")
      (node (ref "C15") (pin "1") (pinfunction "1_1") (pintype "passive"))
      (node (ref "U1") (pin "24") (pinfunction "C1_24") (pintype "bidirectional"))
    )
    (net (code "70") (name "Net-(U1-CAP)") (class "Default")
      (node (ref "C14") (pin "1") (pinfunction "1_1") (pintype "passive"))
      (node (ref "U1") (pin "21") (pinfunction "CAP_21") (pintype "bidirectional"))
    )
    (net (code "71") (name "Net-(U2-CANH)") (class "Default")
      (node (ref "R5") (pin "2") (pinfunction "2_2") (pintype "passive"))
      (node (ref "U2") (pin "7") (pinfunction "CANH_7") (pintype "bidirectional"))
      (node (ref "X1") (pin "7") (pinfunction "7_7") (pintype "passive"))
    )
    (net (code "72") (name "Net-(U2-CANL)") (class "Default")
      (node (ref "R5") (pin "1") (pinfunction "1_1") (pintype "passive"))
      (node (ref "U2") (pin "6") (pinfunction "CANL_6") (pintype "bidirectional"))
      (node (ref "X1") (pin "2") (pinfunction "2_2") (pintype "passive"))
    )
    (net (code "73") (name "Net-(U2-RS)") (class "Default")
      (node (ref "JP3") (pin "2") (pinfunction "2_2") (pintype "passive"))
      (node (ref "R4") (pin "2") (pinfunction "2_2") (pintype "passive"))
      (node (ref "U2") (pin "8") (pinfunction "RS_8") (pintype "bidirectional"))
    )
    (net (code "74") (name "VCC") (class "Default")
      (node (ref "C8") (pin "+") (pinfunction "+_+") (pintype "passive"))
      (node (ref "CN1") (pin "PWR1") (pinfunction "PWR_PWR1") (pintype "power_in"))
      (node (ref "IC1") (pin "3") (pinfunction "IN_3") (pintype "input"))
    )
    (net (code "75") (name "unconnected-(IC2A-NC-Pad73)") (class "Default")
      (node (ref "IC2") (pin "73") (pinfunction "NC_73") (pintype "no_connect"))
    )
    (net (code "76") (name "unconnected-(IC2B-OSC_IN-Pad12)") (class "Default")
      (node (ref "IC2") (pin "12") (pinfunction "OSC_IN_12") (pintype "input"))
    )
    (net (code "77") (name "unconnected-(IC2B-OSC_OUT-Pad13)") (class "Default")
      (node (ref "IC2") (pin "13") (pinfunction "OSC_OUT_13") (pintype "output"))
    )
    (net (code "78") (name "unconnected-(IC2C-PA8-Pad67)") (class "Default")
      (node (ref "IC2") (pin "67") (pinfunction "PA8_67") (pintype "bidirectional"))
    )
    (net (code "79") (name "unconnected-(IC2C-PA9-Pad68)") (class "Default")
      (node (ref "IC2") (pin "68") (pinfunction "PA9_68") (pintype "bidirectional"))
    )
    (net (code "80") (name "unconnected-(IC2C-PA10-Pad69)") (class "Default")
      (node (ref "IC2") (pin "69") (pinfunction "PA10_69") (pintype "bidirectional"))
    )
    (net (code "81") (name "unconnected-(IC2C-PA15-Pad77)") (class "Default")
      (node (ref "IC2") (pin "77") (pinfunction "PA15_77") (pintype "bidirectional"))
    )
    (net (code "82") (name "unconnected-(IC2D-PA5-Pad30)") (class "Default")
      (node (ref "IC2") (pin "30") (pinfunction "PA5_30") (pintype "bidirectional"))
    )
    (net (code "83") (name "unconnected-(IC2D-PA6-Pad31)") (class "Default")
      (node (ref "IC2") (pin "31") (pinfunction "PA6_31") (pintype "bidirectional"))
    )
    (net (code "84") (name "unconnected-(IC2D-PA7-Pad32)") (class "Default")
      (node (ref "IC2") (pin "32") (pinfunction "PA7_32") (pintype "bidirectional"))
    )
    (net (code "85") (name "unconnected-(IC2E-PB9-Pad96)") (class "Default")
      (node (ref "IC2") (pin "96") (pinfunction "PB9_96") (pintype "bidirectional"))
    )
    (net (code "86") (name "unconnected-(IC2E-PB14-Pad53)") (class "Default")
      (node (ref "IC2") (pin "53") (pinfunction "PB14_53") (pintype "bidirectional"))
    )
    (net (code "87") (name "unconnected-(IC2E-PB15-Pad54)") (class "Default")
      (node (ref "IC2") (pin "54") (pinfunction "PB15_54") (pintype "bidirectional"))
    )
    (net (code "88") (name "unconnected-(IC2F-PB0-Pad35)") (class "Default")
      (node (ref "IC2") (pin "35") (pinfunction "PB0_35") (pintype "bidirectional"))
    )
    (net (code "89") (name "unconnected-(IC2F-PB1-Pad36)") (class "Default")
      (node (ref "IC2") (pin "36") (pinfunction "PB1_36") (pintype "bidirectional"))
    )
    (net (code "90") (name "unconnected-(IC2F-PB2-Pad37)") (class "Default")
      (node (ref "IC2") (pin "37") (pinfunction "PB2_37") (pintype "bidirectional"))
    )
    (net (code "91") (name "unconnected-(IC2G-PC10-Pad78)") (class "Default")
      (node (ref "IC2") (pin "78") (pinfunction "PC10_78") (pintype "bidirectional"))
    )
    (net (code "92") (name "unconnected-(IC2G-PC11-Pad79)") (class "Default")
      (node (ref "IC2") (pin "79") (pinfunction "PC11_79") (pintype "bidirectional"))
    )
    (net (code "93") (name "unconnected-(IC2G-PC12-Pad80)") (class "Default")
      (node (ref "IC2") (pin "80") (pinfunction "PC12_80") (pintype "bidirectional"))
    )
    (net (code "94") (name "unconnected-(IC2G-PC13-Pad7)") (class "Default")
      (node (ref "IC2") (pin "7") (pinfunction "PC13_7") (pintype "bidirectional"))
    )
    (net (code "95") (name "unconnected-(IC2G-PC14-Pad8)") (class "Default")
      (node (ref "IC2") (pin "8") (pinfunction "PC14_8") (pintype "bidirectional"))
    )
    (net (code "96") (name "unconnected-(IC2G-PC15-Pad9)") (class "Default")
      (node (ref "IC2") (pin "9") (pinfunction "PC15_9") (pintype "bidirectional"))
    )
    (net (code "97") (name "unconnected-(IC2H-PC0-Pad15)") (class "Default")
      (node (ref "IC2") (pin "15") (pinfunction "PC0_15") (pintype "bidirectional"))
    )
    (net (code "98") (name "unconnected-(IC2H-PC4-Pad33)") (class "Default")
      (node (ref "IC2") (pin "33") (pinfunction "PC4_33") (pintype "bidirectional"))
    )
    (net (code "99") (name "unconnected-(IC2H-PC5-Pad34)") (class "Default")
      (node (ref "IC2") (pin "34") (pinfunction "PC5_34") (pintype "bidirectional"))
    )
    (net (code "100") (name "unconnected-(IC2H-PC6-Pad63)") (class "Default")
      (node (ref "IC2") (pin "63") (pinfunction "PC6_63") (pintype "bidirectional"))
    )
    (net (code "101") (name "unconnected-(IC2H-PC7-Pad64)") (class "Default")
      (node (ref "IC2") (pin "64") (pinfunction "PC7_64") (pintype "bidirectional"))
    )
    (net (code "102") (name "unconnected-(IC2I-PD13-Pad60)") (class "Default")
      (node (ref "IC2") (pin "60") (pinfunction "PD13_60") (pintype "bidirectional"))
    )
    (net (code "103") (name "unconnected-(IC2I-PD14-Pad61)") (class "Default")
      (node (ref "IC2") (pin "61") (pinfunction "PD14_61") (pintype "bidirectional"))
    )
    (net (code "104") (name "unconnected-(IC2I-PD15-Pad62)") (class "Default")
      (node (ref "IC2") (pin "62") (pinfunction "PD15_62") (pintype "bidirectional"))
    )
    (net (code "105") (name "unconnected-(IC2J-PD6-Pad87)") (class "Default")
      (node (ref "IC2") (pin "87") (pinfunction "PD6_87") (pintype "bidirectional"))
    )
    (net (code "106") (name "unconnected-(IC2J-PD7-Pad88)") (class "Default")
      (node (ref "IC2") (pin "88") (pinfunction "PD7_88") (pintype "bidirectional"))
    )
    (net (code "107") (name "unconnected-(IC2K-PE8-Pad39)") (class "Default")
      (node (ref "IC2") (pin "39") (pinfunction "PE8_39") (pintype "bidirectional"))
    )
    (net (code "108") (name "unconnected-(IC2K-PE9-Pad40)") (class "Default")
      (node (ref "IC2") (pin "40") (pinfunction "PE9_40") (pintype "bidirectional"))
    )
    (net (code "109") (name "unconnected-(IC2K-PE10-Pad41)") (class "Default")
      (node (ref "IC2") (pin "41") (pinfunction "PE10_41") (pintype "bidirectional"))
    )
    (net (code "110") (name "unconnected-(IC2K-PE11-Pad42)") (class "Default")
      (node (ref "IC2") (pin "42") (pinfunction "PE11_42") (pintype "bidirectional"))
    )
    (net (code "111") (name "unconnected-(IC2K-PE12-Pad43)") (class "Default")
      (node (ref "IC2") (pin "43") (pinfunction "PE12_43") (pintype "bidirectional"))
    )
    (net (code "112") (name "unconnected-(IC2K-PE13-Pad44)") (class "Default")
      (node (ref "IC2") (pin "44") (pinfunction "PE13_44") (pintype "bidirectional"))
    )
    (net (code "113") (name "unconnected-(IC2K-PE14-Pad45)") (class "Default")
      (node (ref "IC2") (pin "45") (pinfunction "PE14_45") (pintype "bidirectional"))
    )
    (net (code "114") (name "unconnected-(IC2K-PE15-Pad46)") (class "Default")
      (node (ref "IC2") (pin "46") (pinfunction "PE15_46") (pintype "bidirectional"))
    )
    (net (code "115") (name "unconnected-(IC2L-PE0-Pad97)") (class "Default")
      (node (ref "IC2") (pin "97") (pinfunction "PE0_97") (pintype "bidirectional"))
    )
    (net (code "116") (name "unconnected-(IC2L-PE1-Pad98)") (class "Default")
      (node (ref "IC2") (pin "98") (pinfunction "PE1_98") (pintype "bidirectional"))
    )
    (net (code "117") (name "unconnected-(IC2L-PE2-Pad1)") (class "Default")
      (node (ref "IC2") (pin "1") (pinfunction "PE2_1") (pintype "bidirectional"))
    )
    (net (code "118") (name "unconnected-(IC2L-PE3-Pad2)") (class "Default")
      (node (ref "IC2") (pin "2") (pinfunction "PE3_2") (pintype "bidirectional"))
    )
    (net (code "119") (name "unconnected-(IC2L-PE4-Pad3)") (class "Default")
      (node (ref "IC2") (pin "3") (pinfunction "PE4_3") (pintype "bidirectional"))
    )
    (net (code "120") (name "unconnected-(IC2L-PE5-Pad4)") (class "Default")
      (node (ref "IC2") (pin "4") (pinfunction "PE5_4") (pintype "bidirectional"))
    )
    (net (code "121") (name "unconnected-(IC2L-PE6-Pad5)") (class "Default")
      (node (ref "IC2") (pin "5") (pinfunction "PE6_5") (pintype "bidirectional"))
    )
    (net (code "122") (name "unconnected-(IC2L-PE7-Pad38)") (class "Default")
      (node (ref "IC2") (pin "38") (pinfunction "PE7_38") (pintype "bidirectional"))
    )
    (net (code "123") (name "unconnected-(IC3-CLK2MAC-Pad25)") (class "Default")
      (node (ref "IC3") (pin "25") (pinfunction "CLK2MAC_25") (pintype "bidirectional"))
    )
    (net (code "124") (name "unconnected-(IC3-LED_ACTCOL-Pad26)") (class "Default")
      (node (ref "IC3") (pin "26") (pinfunction "LED_ACTCOL_26") (pintype "bidirectional"))
    )
    (net (code "125") (name "unconnected-(IC3-PWRDN_INTN-Pad7)") (class "Default")
      (node (ref "IC3") (pin "7") (pinfunction "PWRDN_INTN_7") (pintype "bidirectional"))
    )
    (net (code "126") (name "unconnected-(IC3-TCK-Pad8)") (class "Default")
      (node (ref "IC3") (pin "8") (pinfunction "TCK_8") (pintype "input"))
    )
    (net (code "127") (name "unconnected-(IC3-TDI-Pad12)") (class "Default")
      (node (ref "IC3") (pin "12") (pinfunction "TDI_12") (pintype "input"))
    )
    (net (code "128") (name "unconnected-(IC3-TDO-Pad9)") (class "Default")
      (node (ref "IC3") (pin "9") (pinfunction "TDO_9") (pintype "output"))
    )
    (net (code "129") (name "unconnected-(IC3-TMS-Pad10)") (class "Default")
      (node (ref "IC3") (pin "10") (pinfunction "TMS_10") (pintype "input"))
    )
    (net (code "130") (name "unconnected-(IC3-TRST_N-Pad11)") (class "Default")
      (node (ref "IC3") (pin "11") (pinfunction "TRST_N_11") (pintype "input"))
    )
    (net (code "131") (name "unconnected-(J1-NC-Pad7)") (class "Default")
      (node (ref "J1") (pin "7") (pinfunction "NC_7") (pintype "no_connect"))
    )
    (net (code "132") (name "unconnected-(JP4-Pad1)") (class "Default")
      (node (ref "JP4") (pin "1") (pinfunction "1_1") (pintype "passive"))
    )
    (net (code "133") (name "unconnected-(U1-DEN_A{slash}G-Pad13)") (class "Default")
      (node (ref "U1") (pin "13") (pinfunction "DEN_A/G_13") (pintype "bidirectional"))
    )
    (net (code "134") (name "unconnected-(U1-DRDY_M-Pad9)") (class "Default")
      (node (ref "U1") (pin "9") (pinfunction "DRDY_M_9") (pintype "bidirectional"))
    )
    (net (code "135") (name "unconnected-(U1-INT1_A{slash}G-Pad11)") (class "Default")
      (node (ref "U1") (pin "11") (pinfunction "INT1_A/G_11") (pintype "bidirectional"))
    )
    (net (code "136") (name "unconnected-(U1-INT2_A{slash}G-Pad12)") (class "Default")
      (node (ref "U1") (pin "12") (pinfunction "INT2_A/G_12") (pintype "bidirectional"))
    )
    (net (code "137") (name "unconnected-(U1-INT_M-Pad10)") (class "Default")
      (node (ref "U1") (pin "10") (pinfunction "INT_M_10") (pintype "bidirectional"))
    )
    (net (code "138") (name "unconnected-(U2-VREF-Pad5)") (class "Default")
      (node (ref "U2") (pin "5") (pinfunction "VREF_5") (pintype "bidirectional"))
    )
    (net (code "139") (name "unconnected-(X1-Pad1)") (class "Default")
      (node (ref "X1") (pin "1") (pinfunction "1_1") (pintype "passive"))
    )
    (net (code "140") (name "unconnected-(X1-Pad4)") (class "Default")
      (node (ref "X1") (pin "4") (pinfunction "4_4") (pintype "passive"))
    )
    (net (code "141") (name "unconnected-(X1-Pad8)") (class "Default")
      (node (ref "X1") (pin "8") (pinfunction "8_8") (pintype "passive"))
    )
    (net (code "142") (name "unconnected-(X1-Pad9)") (class "Default")
      (node (ref "X1") (pin "9") (pinfunction "9_9") (pintype "passive"))
    )
  )
)
